# 14_NTC_TEMPSENSOR.net
KiCad netlist of a schematic drawn in Altium Designer
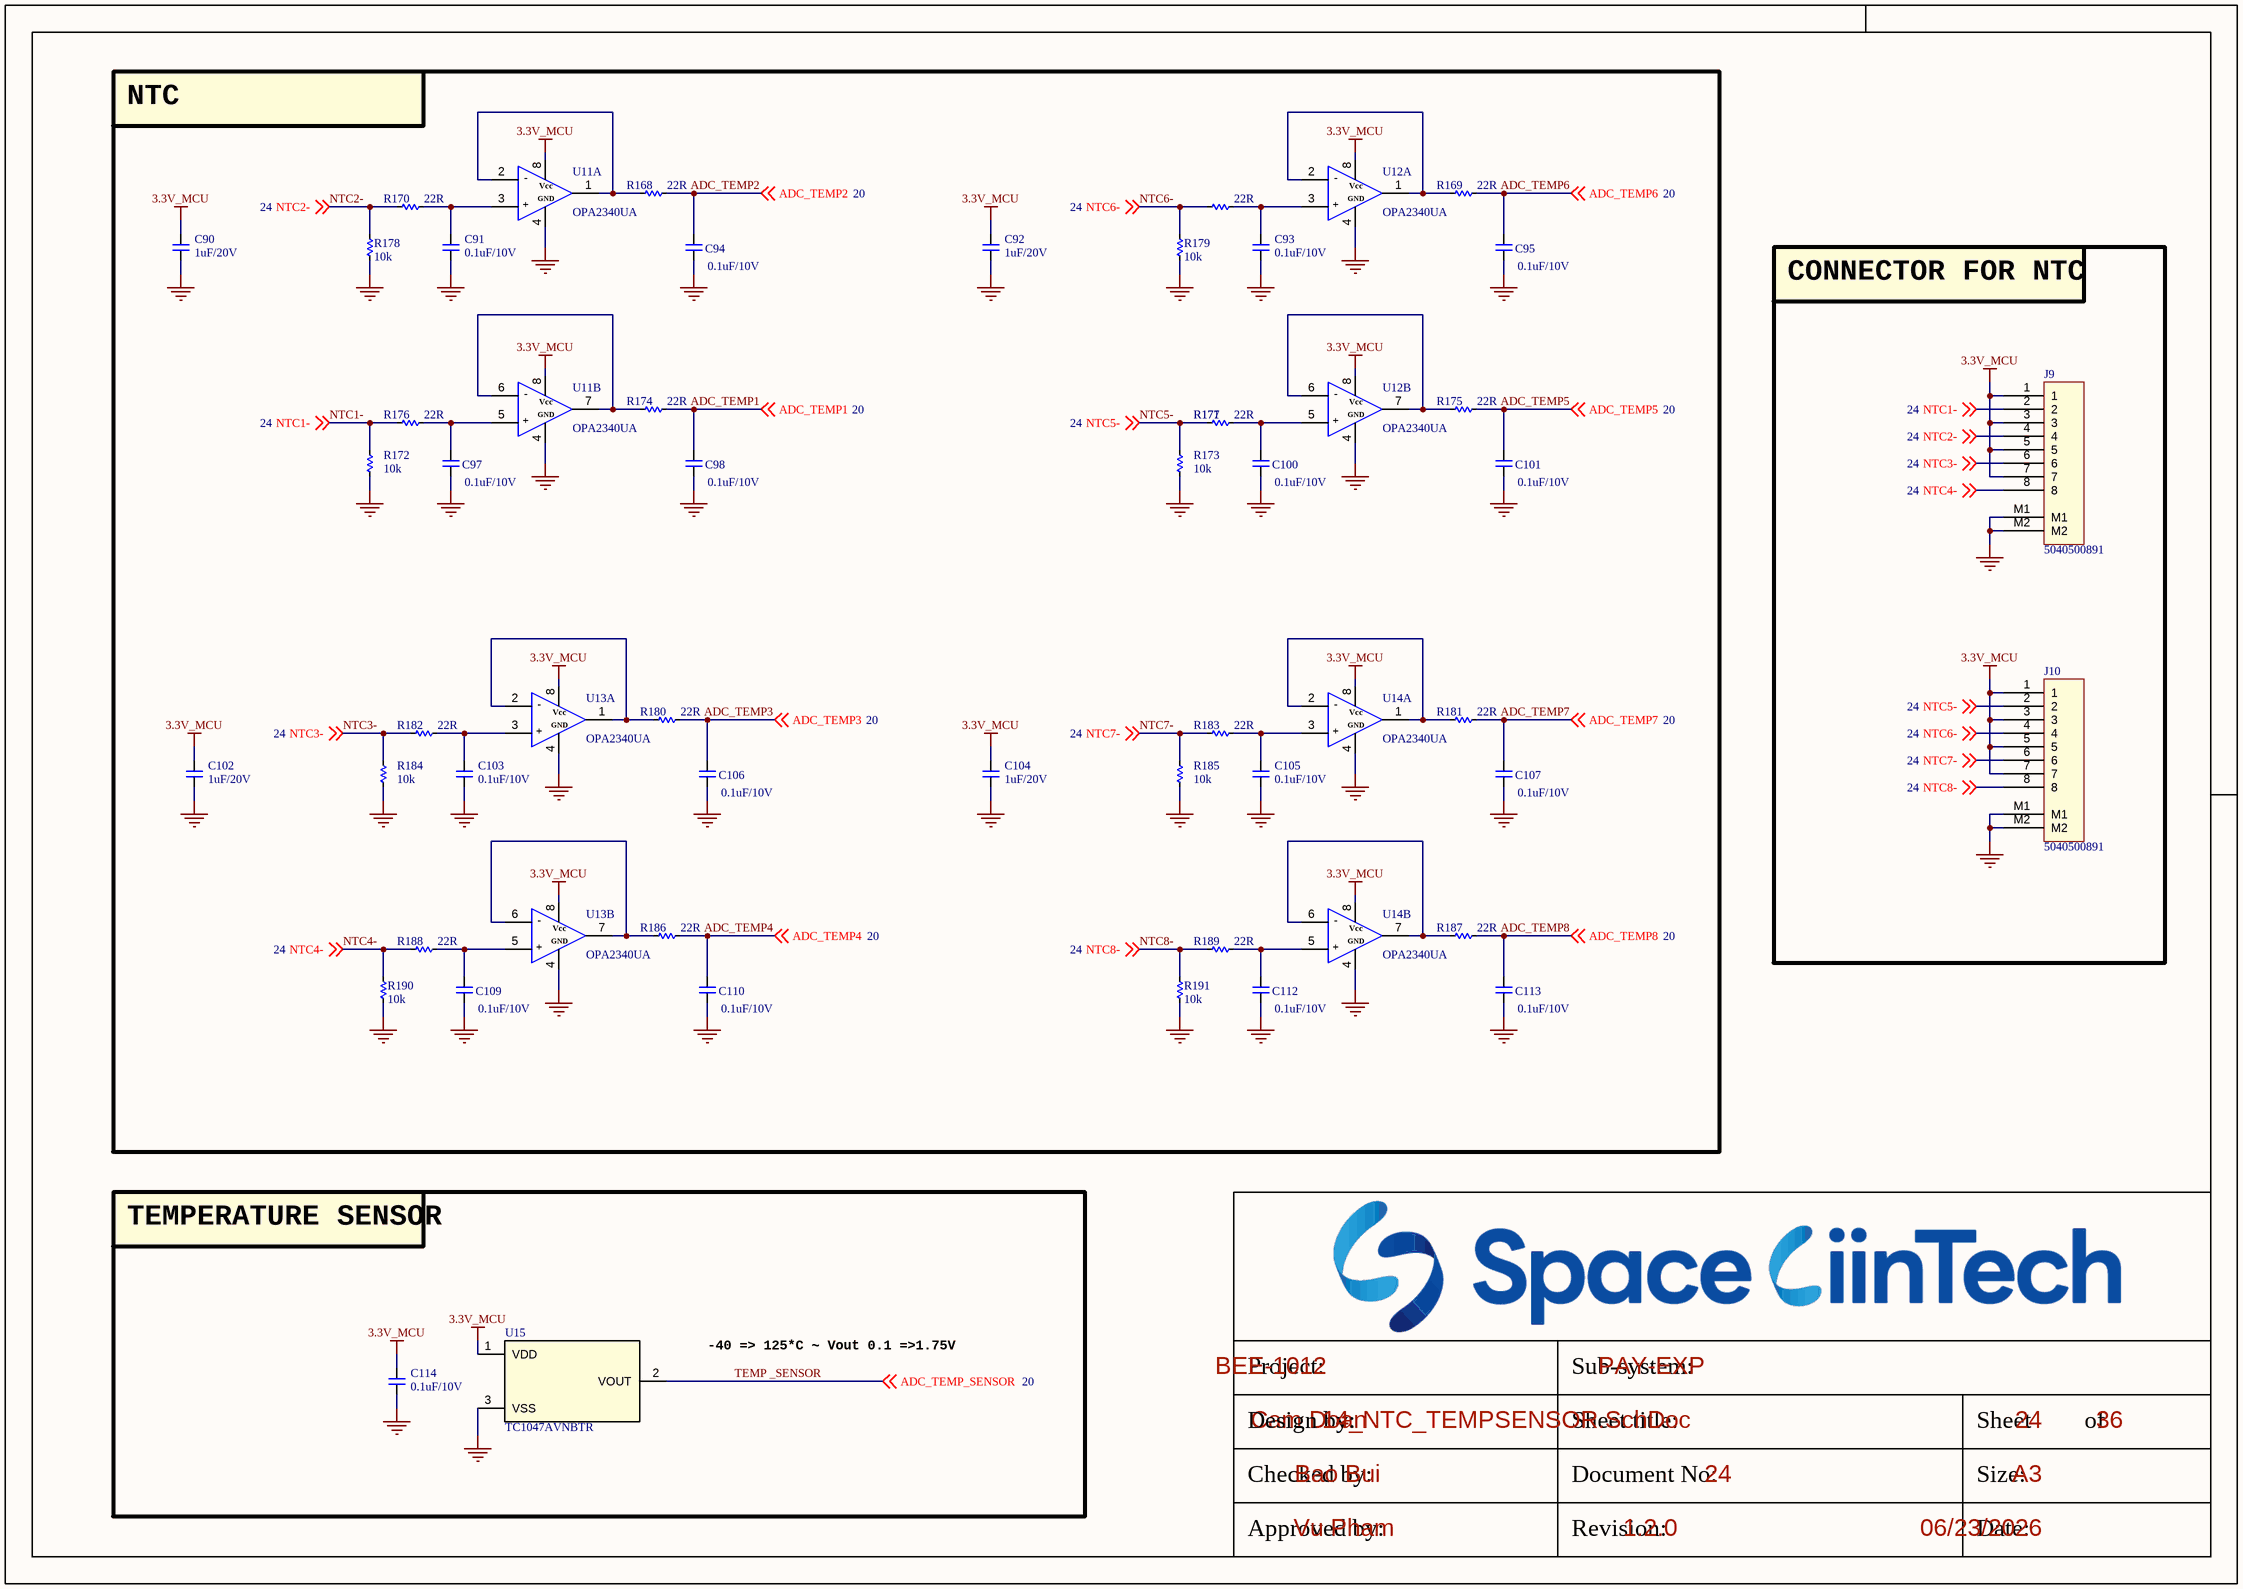
[diagram p0: 14_NTC_TEMPSENSOR.SchDoc]

(export (version "E")
  (design (tool "Eeschema 10.0.6"))
  (components
    (comp (ref "C90")
      (value "1uF/20V")
      (footprint "CAP_C_1005X60")
      (description "CAP")
      (libsource (lib "LABLIB") (part "_CAP_C_2"))
    )
    (comp (ref "C91")
      (value "0.1uF/10V")
      (footprint "CAP_C_1005X60")
      (description "CAP")
      (libsource (lib "LABLIB") (part "_CAP_C_2"))
    )
    (comp (ref "C92")
      (value "1uF/20V")
      (footprint "CAP_C_1005X60")
      (description "CAP")
      (libsource (lib "LABLIB") (part "_CAP_C_2"))
    )
    (comp (ref "C93")
      (value "0.1uF/10V")
      (footprint "CAP_C_1005X60")
      (description "CAP")
      (libsource (lib "LABLIB") (part "_CAP_C_2"))
    )
    (comp (ref "C94")
      (value "0.1uF/10V")
      (footprint "CAP_C_1005X60")
      (description "CAP")
      (libsource (lib "LABLIB") (part "_CAP_C_2"))
    )
    (comp (ref "C95")
      (value "0.1uF/10V")
      (footprint "CAP_C_1005X60")
      (description "CAP")
      (libsource (lib "LABLIB") (part "_CAP_C_2"))
    )
    (comp (ref "C97")
      (value "0.1uF/10V")
      (footprint "CAP_C_1005X60")
      (description "CAP")
      (libsource (lib "LABLIB") (part "_CAP_C_2"))
    )
    (comp (ref "C98")
      (value "0.1uF/10V")
      (footprint "CAP_C_1005X60")
      (description "CAP")
      (libsource (lib "LABLIB") (part "_CAP_C_2"))
    )
    (comp (ref "C100")
      (value "0.1uF/10V")
      (footprint "CAP_C_1005X60")
      (description "CAP")
      (libsource (lib "LABLIB") (part "_CAP_C_2"))
    )
    (comp (ref "C101")
      (value "0.1uF/10V")
      (footprint "CAP_C_1005X60")
      (description "CAP")
      (libsource (lib "LABLIB") (part "_CAP_C_2"))
    )
    (comp (ref "C102")
      (value "1uF/20V")
      (footprint "CAP_C_1005X60")
      (description "CAP")
      (libsource (lib "LABLIB") (part "_CAP_C_2"))
    )
    (comp (ref "C103")
      (value "0.1uF/10V")
      (footprint "CAP_C_1005X60")
      (description "CAP")
      (libsource (lib "LABLIB") (part "_CAP_C_2"))
    )
    (comp (ref "C104")
      (value "1uF/20V")
      (footprint "CAP_C_1005X60")
      (description "CAP")
      (libsource (lib "LABLIB") (part "_CAP_C_2"))
    )
    (comp (ref "C105")
      (value "0.1uF/10V")
      (footprint "CAP_C_1005X60")
      (description "CAP")
      (libsource (lib "LABLIB") (part "_CAP_C_2"))
    )
    (comp (ref "C106")
      (value "0.1uF/10V")
      (footprint "CAP_C_1005X60")
      (description "CAP")
      (libsource (lib "LABLIB") (part "_CAP_C_2"))
    )
    (comp (ref "C107")
      (value "0.1uF/10V")
      (footprint "CAP_C_1005X60")
      (description "CAP")
      (libsource (lib "LABLIB") (part "_CAP_C_2"))
    )
    (comp (ref "C109")
      (value "0.1uF/10V")
      (footprint "CAP_C_1005X60")
      (description "CAP")
      (libsource (lib "LABLIB") (part "_CAP_C_2"))
    )
    (comp (ref "C110")
      (value "0.1uF/10V")
      (footprint "CAP_C_1005X60")
      (description "CAP")
      (libsource (lib "LABLIB") (part "_CAP_C_2"))
    )
    (comp (ref "C112")
      (value "0.1uF/10V")
      (footprint "CAP_C_1005X60")
      (description "CAP")
      (libsource (lib "LABLIB") (part "_CAP_C_2"))
    )
    (comp (ref "C113")
      (value "0.1uF/10V")
      (footprint "CAP_C_1005X60")
      (description "CAP")
      (libsource (lib "LABLIB") (part "_CAP_C_2"))
    )
    (comp (ref "C114")
      (value "0.1uF/10V")
      (footprint "CAP_C_1005X60")
      (description "CAP")
      (libsource (lib "LABLIB") (part "_CAP_C_2"))
    )
    (comp (ref "J9")
      (value "5040500891")
      (footprint "MOLEX_5040500891")
      (libsource (lib "LABLIB") (part "Header 8x1_2M"))
    )
    (comp (ref "J10")
      (value "5040500891")
      (footprint "MOLEX_5040500891")
      (libsource (lib "LABLIB") (part "Header 8x1_2M"))
    )
    (comp (ref "R168")
      (value "22R")
      (footprint "RES_C_1005X40")
      (description "RES")
      (libsource (lib "LABLIB") (part "_RES_B_2"))
    )
    (comp (ref "R169")
      (value "22R")
      (footprint "RES_C_1005X40")
      (description "RES")
      (libsource (lib "LABLIB") (part "_RES_B_2"))
    )
    (comp (ref "R170")
      (value "22R")
      (footprint "RES_C_1005X40")
      (description "RES")
      (libsource (lib "LABLIB") (part "_RES_B_2"))
    )
    (comp (ref "R171")
      (value "22R")
      (footprint "RES_C_1005X40")
      (description "RES")
      (libsource (lib "LABLIB") (part "_RES_B_2"))
    )
    (comp (ref "R172")
      (value "10k")
      (footprint "RES_C_1005X40")
      (description "RES")
      (libsource (lib "LABLIB") (part "_RES_B_2"))
    )
    (comp (ref "R173")
      (value "10k")
      (footprint "RES_C_1005X40")
      (description "RES")
      (libsource (lib "LABLIB") (part "_RES_B_2"))
    )
    (comp (ref "R174")
      (value "22R")
      (footprint "RES_C_1005X40")
      (description "RES")
      (libsource (lib "LABLIB") (part "_RES_B_2"))
    )
    (comp (ref "R175")
      (value "22R")
      (footprint "RES_C_1005X40")
      (description "RES")
      (libsource (lib "LABLIB") (part "_RES_B_2"))
    )
    (comp (ref "R176")
      (value "22R")
      (footprint "RES_C_1005X40")
      (description "RES")
      (libsource (lib "LABLIB") (part "_RES_B_2"))
    )
    (comp (ref "R177")
      (value "22R")
      (footprint "RES_C_1005X40")
      (description "RES")
      (libsource (lib "LABLIB") (part "_RES_B_2"))
    )
    (comp (ref "R178")
      (value "10k")
      (footprint "RES_C_1005X40")
      (description "RES")
      (libsource (lib "LABLIB") (part "_RES_B_2"))
    )
    (comp (ref "R179")
      (value "10k")
      (footprint "RES_C_1005X40")
      (description "RES")
      (libsource (lib "LABLIB") (part "_RES_B_2"))
    )
    (comp (ref "R180")
      (value "22R")
      (footprint "RES_C_1005X40")
      (description "RES")
      (libsource (lib "LABLIB") (part "_RES_B_2"))
    )
    (comp (ref "R181")
      (value "22R")
      (footprint "RES_C_1005X40")
      (description "RES")
      (libsource (lib "LABLIB") (part "_RES_B_2"))
    )
    (comp (ref "R182")
      (value "22R")
      (footprint "RES_C_1005X40")
      (description "RES")
      (libsource (lib "LABLIB") (part "_RES_B_2"))
    )
    (comp (ref "R183")
      (value "22R")
      (footprint "RES_C_1005X40")
      (description "RES")
      (libsource (lib "LABLIB") (part "_RES_B_2"))
    )
    (comp (ref "R184")
      (value "10k")
      (footprint "RES_C_1005X40")
      (description "RES")
      (libsource (lib "LABLIB") (part "_RES_B_2"))
    )
    (comp (ref "R185")
      (value "10k")
      (footprint "RES_C_1005X40")
      (description "RES")
      (libsource (lib "LABLIB") (part "_RES_B_2"))
    )
    (comp (ref "R186")
      (value "22R")
      (footprint "RES_C_1005X40")
      (description "RES")
      (libsource (lib "LABLIB") (part "_RES_B_2"))
    )
    (comp (ref "R187")
      (value "22R")
      (footprint "RES_C_1005X40")
      (description "RES")
      (libsource (lib "LABLIB") (part "_RES_B_2"))
    )
    (comp (ref "R188")
      (value "22R")
      (footprint "RES_C_1005X40")
      (description "RES")
      (libsource (lib "LABLIB") (part "_RES_B_2"))
    )
    (comp (ref "R189")
      (value "22R")
      (footprint "RES_C_1005X40")
      (description "RES")
      (libsource (lib "LABLIB") (part "_RES_B_2"))
    )
    (comp (ref "R190")
      (value "10k")
      (footprint "RES_C_1005X40")
      (description "RES")
      (libsource (lib "LABLIB") (part "_RES_B_2"))
    )
    (comp (ref "R191")
      (value "10k")
      (footprint "RES_C_1005X40")
      (description "RES")
      (libsource (lib "LABLIB") (part "_RES_B_2"))
    )
    (comp (ref "U11")
      (value "OPA2340UA")
      (footprint "SOIC127P602X173-8N")
      (libsource (lib "EXP_HW_V3") (part "OPA2340UA"))
    )
    (comp (ref "U12")
      (value "OPA2340UA")
      (footprint "SOIC127P602X173-8N")
      (libsource (lib "EXP_HW_V3") (part "OPA2340UA"))
    )
    (comp (ref "U13")
      (value "OPA2340UA")
      (footprint "SOIC127P602X173-8N")
      (libsource (lib "EXP_HW_V3") (part "OPA2340UA"))
    )
    (comp (ref "U14")
      (value "OPA2340UA")
      (footprint "SOIC127P602X173-8N")
      (libsource (lib "EXP_HW_V3") (part "OPA2340UA"))
    )
    (comp (ref "U15")
      (value "TC1047AVNBTR")
      (footprint "SOT95P240X120-3N")
      (description "Temperature Sensor Analog, Local -40°C ~ 125°C 10mV/°C SOT-23-3")
      (libsource (lib "LABLIB") (part "IC_SENSOR_TC1047AVNBTR"))
    )
  )
  (nets
    (net (code "1") (name "3.3V_MCU") (class "Default")
      (node (ref "C102") (pin "2") (pinfunction "2_2") (pintype "passive"))
      (node (ref "C104") (pin "2") (pinfunction "2_2") (pintype "passive"))
      (node (ref "C114") (pin "2") (pinfunction "2_2") (pintype "passive"))
      (node (ref "C90") (pin "2") (pinfunction "2_2") (pintype "passive"))
      (node (ref "C92") (pin "2") (pinfunction "2_2") (pintype "passive"))
      (node (ref "J10") (pin "1") (pinfunction "1_1") (pintype "passive"))
      (node (ref "J10") (pin "3") (pinfunction "3_3") (pintype "passive"))
      (node (ref "J10") (pin "5") (pinfunction "5_5") (pintype "passive"))
      (node (ref "J10") (pin "7") (pinfunction "7_7") (pintype "passive"))
      (node (ref "J9") (pin "1") (pinfunction "1_1") (pintype "passive"))
      (node (ref "J9") (pin "3") (pinfunction "3_3") (pintype "passive"))
      (node (ref "J9") (pin "5") (pinfunction "5_5") (pintype "passive"))
      (node (ref "J9") (pin "7") (pinfunction "7_7") (pintype "passive"))
      (node (ref "U11") (pin "8") (pinfunction "8_8") (pintype "passive"))
      (node (ref "U12") (pin "8") (pinfunction "8_8") (pintype "passive"))
      (node (ref "U13") (pin "8") (pinfunction "8_8") (pintype "passive"))
      (node (ref "U14") (pin "8") (pinfunction "8_8") (pintype "passive"))
      (node (ref "U15") (pin "1") (pinfunction "VDD_1") (pintype "passive"))
    )
    (net (code "2") (name "ADC_TEMP1") (class "Default")
      (node (ref "C98") (pin "2") (pinfunction "2_2") (pintype "passive"))
      (node (ref "R174") (pin "2") (pinfunction "2_2") (pintype "passive"))
    )
    (net (code "3") (name "ADC_TEMP2") (class "Default")
      (node (ref "C94") (pin "2") (pinfunction "2_2") (pintype "passive"))
      (node (ref "R168") (pin "2") (pinfunction "2_2") (pintype "passive"))
    )
    (net (code "4") (name "ADC_TEMP3") (class "Default")
      (node (ref "C106") (pin "2") (pinfunction "2_2") (pintype "passive"))
      (node (ref "R180") (pin "2") (pinfunction "2_2") (pintype "passive"))
    )
    (net (code "5") (name "ADC_TEMP4") (class "Default")
      (node (ref "C110") (pin "2") (pinfunction "2_2") (pintype "passive"))
      (node (ref "R186") (pin "2") (pinfunction "2_2") (pintype "passive"))
    )
    (net (code "6") (name "ADC_TEMP5") (class "Default")
      (node (ref "C101") (pin "2") (pinfunction "2_2") (pintype "passive"))
      (node (ref "R175") (pin "2") (pinfunction "2_2") (pintype "passive"))
    )
    (net (code "7") (name "ADC_TEMP6") (class "Default")
      (node (ref "C95") (pin "2") (pinfunction "2_2") (pintype "passive"))
      (node (ref "R169") (pin "2") (pinfunction "2_2") (pintype "passive"))
    )
    (net (code "8") (name "ADC_TEMP7") (class "Default")
      (node (ref "C107") (pin "2") (pinfunction "2_2") (pintype "passive"))
      (node (ref "R181") (pin "2") (pinfunction "2_2") (pintype "passive"))
    )
    (net (code "9") (name "ADC_TEMP8") (class "Default")
      (node (ref "C113") (pin "2") (pinfunction "2_2") (pintype "passive"))
      (node (ref "R187") (pin "2") (pinfunction "2_2") (pintype "passive"))
    )
    (net (code "10") (name "ADC_TEMP_SENSOR") (class "Default")
      (node (ref "U15") (pin "2") (pinfunction "VOUT_2") (pintype "passive"))
    )
    (net (code "11") (name "GND") (class "Default")
      (node (ref "C100") (pin "1") (pinfunction "1_1") (pintype "passive"))
      (node (ref "C101") (pin "1") (pinfunction "1_1") (pintype "passive"))
      (node (ref "C102") (pin "1") (pinfunction "1_1") (pintype "passive"))
      (node (ref "C103") (pin "1") (pinfunction "1_1") (pintype "passive"))
      (node (ref "C104") (pin "1") (pinfunction "1_1") (pintype "passive"))
      (node (ref "C105") (pin "1") (pinfunction "1_1") (pintype "passive"))
      (node (ref "C106") (pin "1") (pinfunction "1_1") (pintype "passive"))
      (node (ref "C107") (pin "1") (pinfunction "1_1") (pintype "passive"))
      (node (ref "C109") (pin "1") (pinfunction "1_1") (pintype "passive"))
      (node (ref "C110") (pin "1") (pinfunction "1_1") (pintype "passive"))
      (node (ref "C112") (pin "1") (pinfunction "1_1") (pintype "passive"))
      (node (ref "C113") (pin "1") (pinfunction "1_1") (pintype "passive"))
      (node (ref "C114") (pin "1") (pinfunction "1_1") (pintype "passive"))
      (node (ref "C90") (pin "1") (pinfunction "1_1") (pintype "passive"))
      (node (ref "C91") (pin "1") (pinfunction "1_1") (pintype "passive"))
      (node (ref "C92") (pin "1") (pinfunction "1_1") (pintype "passive"))
      (node (ref "C93") (pin "1") (pinfunction "1_1") (pintype "passive"))
      (node (ref "C94") (pin "1") (pinfunction "1_1") (pintype "passive"))
      (node (ref "C95") (pin "1") (pinfunction "1_1") (pintype "passive"))
      (node (ref "C97") (pin "1") (pinfunction "1_1") (pintype "passive"))
      (node (ref "C98") (pin "1") (pinfunction "1_1") (pintype "passive"))
      (node (ref "J10") (pin "M1") (pinfunction "M1_M1") (pintype "passive"))
      (node (ref "J10") (pin "M2") (pinfunction "M2_M2") (pintype "passive"))
      (node (ref "J9") (pin "M1") (pinfunction "M1_M1") (pintype "passive"))
      (node (ref "J9") (pin "M2") (pinfunction "M2_M2") (pintype "passive"))
      (node (ref "R172") (pin "1") (pinfunction "1_1") (pintype "passive"))
      (node (ref "R173") (pin "1") (pinfunction "1_1") (pintype "passive"))
      (node (ref "R178") (pin "1") (pinfunction "1_1") (pintype "passive"))
      (node (ref "R179") (pin "1") (pinfunction "1_1") (pintype "passive"))
      (node (ref "R184") (pin "1") (pinfunction "1_1") (pintype "passive"))
      (node (ref "R185") (pin "1") (pinfunction "1_1") (pintype "passive"))
      (node (ref "R190") (pin "1") (pinfunction "1_1") (pintype "passive"))
      (node (ref "R191") (pin "1") (pinfunction "1_1") (pintype "passive"))
      (node (ref "U11") (pin "4") (pinfunction "4_4") (pintype "passive"))
      (node (ref "U12") (pin "4") (pinfunction "4_4") (pintype "passive"))
      (node (ref "U13") (pin "4") (pinfunction "4_4") (pintype "passive"))
      (node (ref "U14") (pin "4") (pinfunction "4_4") (pintype "passive"))
      (node (ref "U15") (pin "3") (pinfunction "VSS_3") (pintype "passive"))
    )
    (net (code "12") (name "NTC1-") (class "Default")
      (node (ref "J9") (pin "2") (pinfunction "2_2") (pintype "passive"))
      (node (ref "R172") (pin "2") (pinfunction "2_2") (pintype "passive"))
      (node (ref "R176") (pin "1") (pinfunction "1_1") (pintype "passive"))
    )
    (net (code "13") (name "NTC2-") (class "Default")
      (node (ref "J9") (pin "4") (pinfunction "4_4") (pintype "passive"))
      (node (ref "R170") (pin "1") (pinfunction "1_1") (pintype "passive"))
      (node (ref "R178") (pin "2") (pinfunction "2_2") (pintype "passive"))
    )
    (net (code "14") (name "NTC3-") (class "Default")
      (node (ref "J9") (pin "6") (pinfunction "6_6") (pintype "passive"))
      (node (ref "R182") (pin "1") (pinfunction "1_1") (pintype "passive"))
      (node (ref "R184") (pin "2") (pinfunction "2_2") (pintype "passive"))
    )
    (net (code "15") (name "NTC4-") (class "Default")
      (node (ref "J9") (pin "8") (pinfunction "8_8") (pintype "passive"))
      (node (ref "R188") (pin "1") (pinfunction "1_1") (pintype "passive"))
      (node (ref "R190") (pin "2") (pinfunction "2_2") (pintype "passive"))
    )
    (net (code "16") (name "NTC5-") (class "Default")
      (node (ref "J10") (pin "2") (pinfunction "2_2") (pintype "passive"))
      (node (ref "R173") (pin "2") (pinfunction "2_2") (pintype "passive"))
      (node (ref "R177") (pin "1") (pinfunction "1_1") (pintype "passive"))
    )
    (net (code "17") (name "NTC6-") (class "Default")
      (node (ref "J10") (pin "4") (pinfunction "4_4") (pintype "passive"))
      (node (ref "R171") (pin "1") (pinfunction "1_1") (pintype "passive"))
      (node (ref "R179") (pin "2") (pinfunction "2_2") (pintype "passive"))
    )
    (net (code "18") (name "NTC7-") (class "Default")
      (node (ref "J10") (pin "6") (pinfunction "6_6") (pintype "passive"))
      (node (ref "R183") (pin "1") (pinfunction "1_1") (pintype "passive"))
      (node (ref "R185") (pin "2") (pinfunction "2_2") (pintype "passive"))
    )
    (net (code "19") (name "NTC8-") (class "Default")
      (node (ref "J10") (pin "8") (pinfunction "8_8") (pintype "passive"))
      (node (ref "R189") (pin "1") (pinfunction "1_1") (pintype "passive"))
      (node (ref "R191") (pin "2") (pinfunction "2_2") (pintype "passive"))
    )
    (net (code "20") (name "Net-(C91-Pad2)") (class "Default")
      (node (ref "C91") (pin "2") (pinfunction "2_2") (pintype "passive"))
      (node (ref "R170") (pin "2") (pinfunction "2_2") (pintype "passive"))
      (node (ref "U11") (pin "3") (pinfunction "3_3") (pintype "passive"))
    )
    (net (code "21") (name "Net-(C93-Pad2)") (class "Default")
      (node (ref "C93") (pin "2") (pinfunction "2_2") (pintype "passive"))
      (node (ref "R171") (pin "2") (pinfunction "2_2") (pintype "passive"))
      (node (ref "U12") (pin "3") (pinfunction "3_3") (pintype "passive"))
    )
    (net (code "22") (name "Net-(C97-Pad2)") (class "Default")
      (node (ref "C97") (pin "2") (pinfunction "2_2") (pintype "passive"))
      (node (ref "R176") (pin "2") (pinfunction "2_2") (pintype "passive"))
      (node (ref "U11") (pin "5") (pinfunction "5_5") (pintype "passive"))
    )
    (net (code "23") (name "Net-(C100-Pad2)") (class "Default")
      (node (ref "C100") (pin "2") (pinfunction "2_2") (pintype "passive"))
      (node (ref "R177") (pin "2") (pinfunction "2_2") (pintype "passive"))
      (node (ref "U12") (pin "5") (pinfunction "5_5") (pintype "passive"))
    )
    (net (code "24") (name "Net-(C103-Pad2)") (class "Default")
      (node (ref "C103") (pin "2") (pinfunction "2_2") (pintype "passive"))
      (node (ref "R182") (pin "2") (pinfunction "2_2") (pintype "passive"))
      (node (ref "U13") (pin "3") (pinfunction "3_3") (pintype "passive"))
    )
    (net (code "25") (name "Net-(C105-Pad2)") (class "Default")
      (node (ref "C105") (pin "2") (pinfunction "2_2") (pintype "passive"))
      (node (ref "R183") (pin "2") (pinfunction "2_2") (pintype "passive"))
      (node (ref "U14") (pin "3") (pinfunction "3_3") (pintype "passive"))
    )
    (net (code "26") (name "Net-(C109-Pad2)") (class "Default")
      (node (ref "C109") (pin "2") (pinfunction "2_2") (pintype "passive"))
      (node (ref "R188") (pin "2") (pinfunction "2_2") (pintype "passive"))
      (node (ref "U13") (pin "5") (pinfunction "5_5") (pintype "passive"))
    )
    (net (code "27") (name "Net-(C112-Pad2)") (class "Default")
      (node (ref "C112") (pin "2") (pinfunction "2_2") (pintype "passive"))
      (node (ref "R189") (pin "2") (pinfunction "2_2") (pintype "passive"))
      (node (ref "U14") (pin "5") (pinfunction "5_5") (pintype "passive"))
    )
    (net (code "28") (name "Net-(R168-Pad1)") (class "Default")
      (node (ref "R168") (pin "1") (pinfunction "1_1") (pintype "passive"))
      (node (ref "U11") (pin "1") (pinfunction "1_1") (pintype "passive"))
      (node (ref "U11") (pin "2") (pinfunction "2_2") (pintype "passive"))
    )
    (net (code "29") (name "Net-(R169-Pad1)") (class "Default")
      (node (ref "R169") (pin "1") (pinfunction "1_1") (pintype "passive"))
      (node (ref "U12") (pin "1") (pinfunction "1_1") (pintype "passive"))
      (node (ref "U12") (pin "2") (pinfunction "2_2") (pintype "passive"))
    )
    (net (code "30") (name "Net-(R174-Pad1)") (class "Default")
      (node (ref "R174") (pin "1") (pinfunction "1_1") (pintype "passive"))
      (node (ref "U11") (pin "6") (pinfunction "6_6") (pintype "passive"))
      (node (ref "U11") (pin "7") (pinfunction "7_7") (pintype "passive"))
    )
    (net (code "31") (name "Net-(R175-Pad1)") (class "Default")
      (node (ref "R175") (pin "1") (pinfunction "1_1") (pintype "passive"))
      (node (ref "U12") (pin "6") (pinfunction "6_6") (pintype "passive"))
      (node (ref "U12") (pin "7") (pinfunction "7_7") (pintype "passive"))
    )
    (net (code "32") (name "Net-(R180-Pad1)") (class "Default")
      (node (ref "R180") (pin "1") (pinfunction "1_1") (pintype "passive"))
      (node (ref "U13") (pin "1") (pinfunction "1_1") (pintype "passive"))
      (node (ref "U13") (pin "2") (pinfunction "2_2") (pintype "passive"))
    )
    (net (code "33") (name "Net-(R181-Pad1)") (class "Default")
      (node (ref "R181") (pin "1") (pinfunction "1_1") (pintype "passive"))
      (node (ref "U14") (pin "1") (pinfunction "1_1") (pintype "passive"))
      (node (ref "U14") (pin "2") (pinfunction "2_2") (pintype "passive"))
    )
    (net (code "34") (name "Net-(R186-Pad1)") (class "Default")
      (node (ref "R186") (pin "1") (pinfunction "1_1") (pintype "passive"))
      (node (ref "U13") (pin "6") (pinfunction "6_6") (pintype "passive"))
      (node (ref "U13") (pin "7") (pinfunction "7_7") (pintype "passive"))
    )
    (net (code "35") (name "Net-(R187-Pad1)") (class "Default")
      (node (ref "R187") (pin "1") (pinfunction "1_1") (pintype "passive"))
      (node (ref "U14") (pin "6") (pinfunction "6_6") (pintype "passive"))
      (node (ref "U14") (pin "7") (pinfunction "7_7") (pintype "passive"))
    )
  )
)
